# PowerSupply.net
KiCad netlist of a schematic drawn in Altium Designer
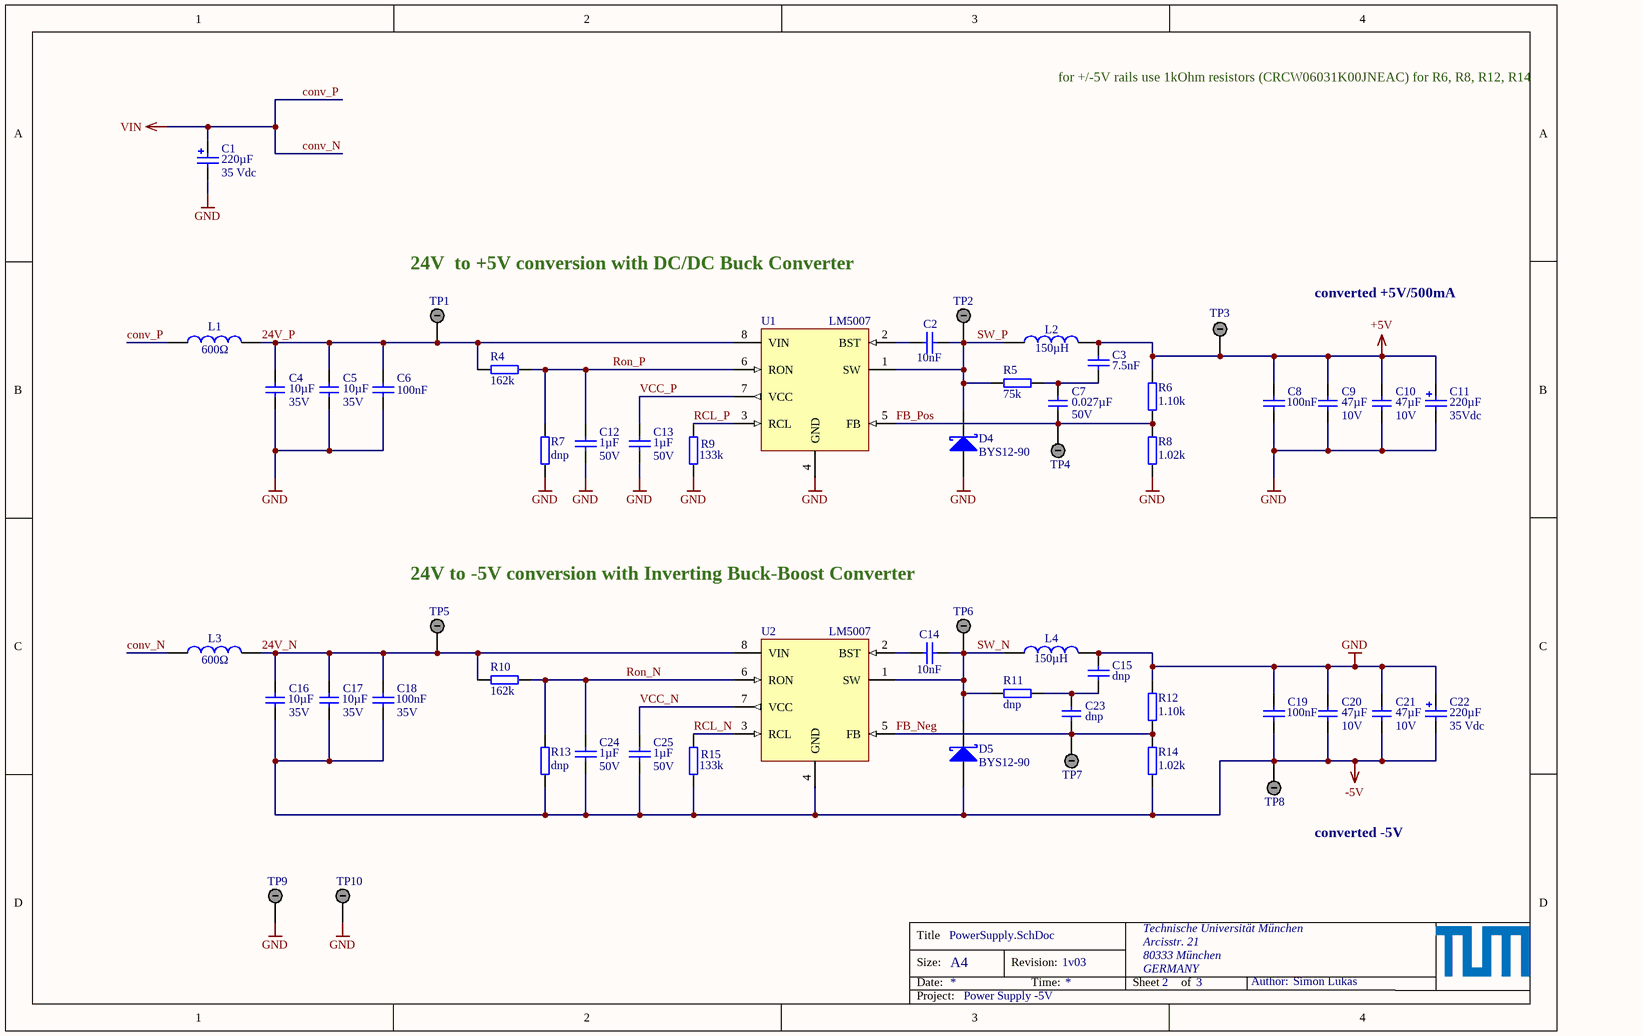
[diagram p0: PowerSupply.SchDoc]

(export (version "E")
  (design (tool "Eeschema 10.0.6"))
  (components
    (comp (ref "C1")
      (value "220µF")
      (footprint "WCAP-ATG5_8x11.5x3.5")
      (description "WCAP-ATG5 Aluminum Electrolytic Capacitors, 8x11.5mm, 35 Vdc, 220 uF")
      (fields
        (field (name "PART NUMBER") "860020574012")
        (field (name "MF") "Würth Elektronik")
        (field (name "VOLTAGE") "35 Vdc")
      )
      (libsource (lib "neg5V") (part "860020574012"))
    )
    (comp (ref "C2")
      (value "10nF")
      (footprint "CAPC1608X07N")
      (fields
        (field (name "MF") "Würth Elektronik")
        (field (name "MPN") "885012206065")
        (field (name "VOLTAGE") "25V")
      )
      (libsource (lib "neg5V") (part "Cap_0603"))
    )
    (comp (ref "C3")
      (value "7.5nF")
      (footprint "CAPC1608X07N")
      (fields
        (field (name "MF") "KEMET")
        (field (name "MPN") "C0603C752J3GACTU")
        (field (name "VOLTAGE") "25V")
      )
      (libsource (lib "neg5V") (part "Cap_0603"))
    )
    (comp (ref "C4")
      (value "10µF")
      (footprint "C_1206")
      (description "Capacitor 1206")
      (fields
        (field (name "TOLERANCE") "10%")
        (field (name "MF") "Murata Electronics")
        (field (name "VOLTAGE") "35V")
      )
      (libsource (lib "neg5V") (part "C_1206"))
    )
    (comp (ref "C5")
      (value "10µF")
      (footprint "C_1206")
      (description "Capacitor 1206")
      (fields
        (field (name "TOLERANCE") "10%")
        (field (name "MF") "Murata Electronics")
        (field (name "VOLTAGE") "35V")
      )
      (libsource (lib "neg5V") (part "C_1206"))
    )
    (comp (ref "C6")
      (value "100nF")
      (footprint "CAPC1608X07N")
      (fields
        (field (name "MF") "Würth Elektronik")
        (field (name "MPN") "885012206071")
        (field (name "VOLTAGE") "25V")
      )
      (libsource (lib "neg5V") (part "Cap_0603"))
    )
    (comp (ref "C7")
      (value "0.027µF")
      (footprint "C_1206")
      (description "Capacitor 1206")
      (fields
        (field (name "TOLERANCE") "5%")
        (field (name "MF") "Murata Electronics")
        (field (name "VOLTAGE") "50V")
      )
      (libsource (lib "neg5V") (part "C_1206"))
    )
    (comp (ref "C8")
      (value "100nF")
      (footprint "CAPC1608X07N")
      (fields
        (field (name "MF") "Würth Elektronik")
        (field (name "MPN") "885012206071")
        (field (name "VOLTAGE") "25V")
      )
      (libsource (lib "neg5V") (part "Cap_0603"))
    )
    (comp (ref "C9")
      (value "47µF")
      (footprint "C_1206")
      (description "Capacitor 1206")
      (fields
        (field (name "TOLERANCE") "20%")
        (field (name "MF") "Murata Electronics")
        (field (name "VOLTAGE") "10V")
      )
      (libsource (lib "neg5V") (part "C_1206"))
    )
    (comp (ref "C10")
      (value "47µF")
      (footprint "C_1206")
      (description "Capacitor 1206")
      (fields
        (field (name "TOLERANCE") "20%")
        (field (name "MF") "Murata Electronics")
        (field (name "VOLTAGE") "10V")
      )
      (libsource (lib "neg5V") (part "C_1206"))
    )
    (comp (ref "C11")
      (value "220µF")
      (footprint "WCAP-ATG5_8x11.5x3.5")
      (description "WCAP-ATG5 Aluminum Electrolytic Capacitors, 8x11.5mm, 35 Vdc, 220 uF")
      (fields
        (field (name "PART NUMBER") "860020574012")
        (field (name "MF") "Würth Elektronik")
        (field (name "VOLTAGE") "35Vdc")
      )
      (libsource (lib "neg5V") (part "860020574012"))
    )
    (comp (ref "C12")
      (value "1µF")
      (footprint "CAPC1608X07N")
      (fields
        (field (name "MF") "Murata Electronics")
        (field (name "MPN") "GRT188R61H105KE13D")
        (field (name "VOLTAGE") "50V")
      )
      (libsource (lib "neg5V") (part "Cap_0603"))
    )
    (comp (ref "C13")
      (value "1µF")
      (footprint "CAPC1608X07N")
      (fields
        (field (name "MF") "Murata Electronics")
        (field (name "MPN") "GRT188R61H105KE13D")
        (field (name "VOLTAGE") "50V")
      )
      (libsource (lib "neg5V") (part "Cap_0603"))
    )
    (comp (ref "C14")
      (value "10nF")
      (footprint "CAPC1608X07N")
      (fields
        (field (name "MF") "Würth Elektronik")
        (field (name "MPN") "885012206065")
        (field (name "VOLTAGE") "25V")
      )
      (libsource (lib "neg5V") (part "Cap_0603"))
    )
    (comp (ref "C15")
      (value "dnp")
      (footprint "CAPC1608X07N")
      (fields
        (field (name "MF") "KEMET")
        (field (name "MPN") "C0603C752J3GACTU")
        (field (name "VOLTAGE") "25V")
      )
      (libsource (lib "neg5V") (part "Cap_0603"))
    )
    (comp (ref "C16")
      (value "10µF")
      (footprint "C_1206")
      (description "Capacitor 1206")
      (fields
        (field (name "TOLERANCE") "10%")
        (field (name "MF") "Murata Electronics")
        (field (name "VOLTAGE") "35V")
      )
      (libsource (lib "neg5V") (part "C_1206"))
    )
    (comp (ref "C17")
      (value "10µF")
      (footprint "C_1206")
      (description "Capacitor 1206")
      (fields
        (field (name "TOLERANCE") "10%")
        (field (name "MF") "Murata Electronics")
        (field (name "VOLTAGE") "35V")
      )
      (libsource (lib "neg5V") (part "C_1206"))
    )
    (comp (ref "C18")
      (value "100nF")
      (footprint "CAPC1608X07N")
      (fields
        (field (name "MF") "Taiyo Yuden")
        (field (name "MPN") "GMK107B7104KAHT")
        (field (name "VOLTAGE") "35V")
        (field (name "TOLERANCE") "10%")
      )
      (libsource (lib "neg5V") (part "Cap_0603"))
    )
    (comp (ref "C19")
      (value "100nF")
      (footprint "CAPC1608X07N")
      (fields
        (field (name "MF") "Würth Elektronik")
        (field (name "MPN") "885012206071")
        (field (name "VOLTAGE") "25V")
      )
      (libsource (lib "neg5V") (part "Cap_0603"))
    )
    (comp (ref "C20")
      (value "47µF")
      (footprint "C_1206")
      (description "Capacitor 1206")
      (fields
        (field (name "TOLERANCE") "20%")
        (field (name "MF") "Murata Electronics")
        (field (name "VOLTAGE") "10V")
      )
      (libsource (lib "neg5V") (part "C_1206"))
    )
    (comp (ref "C21")
      (value "47µF")
      (footprint "C_1206")
      (description "Capacitor 1206")
      (fields
        (field (name "TOLERANCE") "20%")
        (field (name "MF") "Murata Electronics")
        (field (name "VOLTAGE") "10V")
      )
      (libsource (lib "neg5V") (part "C_1206"))
    )
    (comp (ref "C22")
      (value "220µF")
      (footprint "WCAP-ATG5_8x11.5x3.5")
      (description "WCAP-ATG5 Aluminum Electrolytic Capacitors, 8x11.5mm, 35 Vdc, 220 uF")
      (fields
        (field (name "PART NUMBER") "860020574012")
        (field (name "MF") "Würth Elektronik")
        (field (name "VOLTAGE") "35 Vdc")
      )
      (libsource (lib "neg5V") (part "860020574012"))
    )
    (comp (ref "C23")
      (value "dnp")
      (footprint "C_1206")
      (description "Capacitor 1206")
      (fields (field (name "TOLERANCE") "5%") (field (name "MF") "Murata Electronics"))
      (libsource (lib "neg5V") (part "C_1206"))
    )
    (comp (ref "C24")
      (value "1µF")
      (footprint "CAPC1608X07N")
      (fields
        (field (name "MF") "Murata Electronics")
        (field (name "MPN") "GRT188R61H105KE13D")
        (field (name "VOLTAGE") "50V")
      )
      (libsource (lib "neg5V") (part "Cap_0603"))
    )
    (comp (ref "C25")
      (value "1µF")
      (footprint "CAPC1608X07N")
      (fields
        (field (name "MF") "Murata Electronics")
        (field (name "MPN") "GRT188R61H105KE13D")
        (field (name "VOLTAGE") "50V")
      )
      (libsource (lib "neg5V") (part "Cap_0603"))
    )
    (comp (ref "D4")
      (value "BYS12-90")
      (footprint "DIOM4227X23N")
      (description "Schottky Diode")
      (fields (field (name "MF") "Vishay") (field (name "MPN") "BYS12-90-E3/TR3"))
      (libsource (lib "neg5V") (part "BYS12-90"))
    )
    (comp (ref "D5")
      (value "BYS12-90")
      (footprint "DIOM4227X23N")
      (description "Schottky Diode")
      (fields (field (name "MF") "Vishay") (field (name "MPN") "BYS12-90-E3/TR3"))
      (libsource (lib "neg5V") (part "BYS12-90"))
    )
    (comp (ref "L1")
      (value "600Ω")
      (footprint "WE-CBF_0805_High Current")
      (description "WE-CBF SMD EMI Suppression Ferrite Bead, 0805, 600Ω")
      (fields (field (name "MF") "Würth Elektronik") (field (name "MPN") "742792040"))
      (libsource (lib "neg5V") (part "WE-CBF, 742792040"))
    )
    (comp (ref "L2")
      (value "150µH")
      (footprint "SMT_inductor_1050_Performance")
      (description "SMT power Inductor, 150uH, 320m DRC")
      (fields (field (name "MF") "EPCOS / TDK") (field (name "MPN") "B82464G4154M"))
      (libsource (lib "neg5V") (part "B82464G4154M"))
    )
    (comp (ref "L3")
      (value "600Ω")
      (footprint "WE-CBF_0805_High Current")
      (description "WE-CBF SMD EMI Suppression Ferrite Bead, 0805, 600Ω")
      (fields (field (name "MF") "Würth Elektronik") (field (name "MPN") "742792040"))
      (libsource (lib "neg5V") (part "WE-CBF, 742792040"))
    )
    (comp (ref "L4")
      (value "150µH")
      (footprint "SMT_inductor_1050_Performance")
      (description "SMT power Inductor, 150uH, 320m DRC")
      (fields (field (name "MF") "EPCOS / TDK") (field (name "MPN") "B82464G4154M"))
      (libsource (lib "neg5V") (part "B82464G4154M"))
    )
    (comp (ref "R4")
      (value "162k")
      (footprint "RESC1608X06N")
      (fields (field (name "MF") "Bourns") (field (name "MPN") "CR0603-FX-1623ELF"))
      (libsource (lib "neg5V") (part "R_0603"))
    )
    (comp (ref "R5")
      (value "75k")
      (footprint "RESC1608X06N")
      (fields (field (name "MF") "Yageo") (field (name "MPN") "AC0603FR-1375KL"))
      (libsource (lib "neg5V") (part "R_0603"))
    )
    (comp (ref "R6")
      (value "1.10k")
      (footprint "RESC1608X06N")
      (fields
        (field (name "MF") "Vishay / Dale")
        (field (name "MPN") "CRCW06031K10JNEAC")
        (field (name "TOLERANCE") "5%")
      )
      (libsource (lib "neg5V") (part "R_0603"))
    )
    (comp (ref "R7") (value "dnp") (footprint "RESC1608X06N") (libsource (lib "neg5V") (part "R_0603")))
    (comp (ref "R8")
      (value "1.02k")
      (footprint "RESC1608X06N")
      (fields
        (field (name "MF") "Bourns")
        (field (name "MPN") "CR0603-FX-1021ELF")
        (field (name "TOLERANCE") "1%")
      )
      (libsource (lib "neg5V") (part "R_0603"))
    )
    (comp (ref "R9")
      (value "133k")
      (footprint "RESC1608X06N")
      (fields (field (name "MF") "Bourns") (field (name "MPN") "CR0603-FX-1333ELF"))
      (libsource (lib "neg5V") (part "R_0603"))
    )
    (comp (ref "R10")
      (value "162k")
      (footprint "RESC1608X06N")
      (fields (field (name "MF") "Bourns") (field (name "MPN") "CR0603-FX-1623ELF"))
      (libsource (lib "neg5V") (part "R_0603"))
    )
    (comp (ref "R11")
      (value "dnp")
      (footprint "RESC1608X06N")
      (fields (field (name "MF") "Yageo") (field (name "MPN") "AC0603FR-1375KL"))
      (libsource (lib "neg5V") (part "R_0603"))
    )
    (comp (ref "R12")
      (value "1.10k")
      (footprint "RESC1608X06N")
      (fields
        (field (name "MF") "Vishay / Dale")
        (field (name "MPN") "CRCW06031K10JNEAC")
        (field (name "TOLERANCE") "5%")
      )
      (libsource (lib "neg5V") (part "R_0603"))
    )
    (comp (ref "R13") (value "dnp") (footprint "RESC1608X06N") (libsource (lib "neg5V") (part "R_0603")))
    (comp (ref "R14")
      (value "1.02k")
      (footprint "RESC1608X06N")
      (fields
        (field (name "MF") "Bourns")
        (field (name "MPN") "CR0603-FX-1021ELF")
        (field (name "TOLERANCE") "1%")
      )
      (libsource (lib "neg5V") (part "R_0603"))
    )
    (comp (ref "R15")
      (value "133k")
      (footprint "RESC1608X06N")
      (fields (field (name "MF") "Bourns") (field (name "MPN") "CR0603-FX-1333ELF"))
      (libsource (lib "neg5V") (part "R_0603"))
    )
    (comp (ref "TP1")
      (value "24V_P")
      (footprint "TP_5006")
      (description "Test Point;  Compact;  THM;  PC;  .350 L;  .125 OD;  Heat Resistant Nylon 46;  Black")
      (fields
        (field (name "MANUFACTURER") "Keystone Electronics")
        (field (name "MANUFACTURER PART NUMBER") "5006")
      )
      (libsource (lib "neg5V") (part "5006"))
    )
    (comp (ref "TP2")
      (value "SW_P")
      (footprint "TP_5006")
      (description "Test Point;  Compact;  THM;  PC;  .350 L;  .125 OD;  Heat Resistant Nylon 46;  Black")
      (fields
        (field (name "MANUFACTURER") "Keystone Electronics")
        (field (name "MANUFACTURER PART NUMBER") "5006")
      )
      (libsource (lib "neg5V") (part "5006"))
    )
    (comp (ref "TP3")
      (value "+5V")
      (footprint "TP_5006")
      (description "Test Point;  Compact;  THM;  PC;  .350 L;  .125 OD;  Heat Resistant Nylon 46;  Black")
      (fields
        (field (name "MANUFACTURER") "Keystone Electronics")
        (field (name "MANUFACTURER PART NUMBER") "5006")
      )
      (libsource (lib "neg5V") (part "5006"))
    )
    (comp (ref "TP4")
      (value "FB_P")
      (footprint "TP_5006")
      (description "Test Point;  Compact;  THM;  PC;  .350 L;  .125 OD;  Heat Resistant Nylon 46;  Black")
      (fields
        (field (name "MANUFACTURER") "Keystone Electronics")
        (field (name "MANUFACTURER PART NUMBER") "5006")
      )
      (libsource (lib "neg5V") (part "5006"))
    )
    (comp (ref "TP5")
      (value "24V_N")
      (footprint "TP_5006")
      (description "Test Point;  Compact;  THM;  PC;  .350 L;  .125 OD;  Heat Resistant Nylon 46;  Black")
      (fields
        (field (name "MANUFACTURER") "Keystone Electronics")
        (field (name "MANUFACTURER PART NUMBER") "5006")
      )
      (libsource (lib "neg5V") (part "5006"))
    )
    (comp (ref "TP6")
      (value "SW_N")
      (footprint "TP_5006")
      (description "Test Point;  Compact;  THM;  PC;  .350 L;  .125 OD;  Heat Resistant Nylon 46;  Black")
      (fields
        (field (name "MANUFACTURER") "Keystone Electronics")
        (field (name "MANUFACTURER PART NUMBER") "5006")
      )
      (libsource (lib "neg5V") (part "5006"))
    )
    (comp (ref "TP7")
      (value "FB_N")
      (footprint "TP_5006")
      (description "Test Point;  Compact;  THM;  PC;  .350 L;  .125 OD;  Heat Resistant Nylon 46;  Black")
      (fields
        (field (name "MANUFACTURER") "Keystone Electronics")
        (field (name "MANUFACTURER PART NUMBER") "5006")
      )
      (libsource (lib "neg5V") (part "5006"))
    )
    (comp (ref "TP8")
      (value "-5V")
      (footprint "TP_5006")
      (description "Test Point;  Compact;  THM;  PC;  .350 L;  .125 OD;  Heat Resistant Nylon 46;  Black")
      (fields
        (field (name "MANUFACTURER") "Keystone Electronics")
        (field (name "MANUFACTURER PART NUMBER") "5006")
      )
      (libsource (lib "neg5V") (part "5006"))
    )
    (comp (ref "TP9")
      (value "GND")
      (footprint "TP_5006")
      (description "Test Point;  Compact;  THM;  PC;  .350 L;  .125 OD;  Heat Resistant Nylon 46;  Black")
      (fields
        (field (name "MANUFACTURER") "Keystone Electronics")
        (field (name "MANUFACTURER PART NUMBER") "5006")
      )
      (libsource (lib "neg5V") (part "5006"))
    )
    (comp (ref "TP10")
      (value "GND")
      (footprint "TP_5006")
      (description "Test Point;  Compact;  THM;  PC;  .350 L;  .125 OD;  Heat Resistant Nylon 46;  Black")
      (fields
        (field (name "MANUFACTURER") "Keystone Electronics")
        (field (name "MANUFACTURER PART NUMBER") "5006")
      )
      (libsource (lib "neg5V") (part "5006"))
    )
    (comp (ref "U1")
      (value "LM5007")
      (footprint "TSOP65P490X110-8N")
      (description "Buck Converter, 9-75Vin, 2.5-73Vout")
      (fields (field (name "MF") "Texas Instruments") (field (name "MPN") "LM5007MM/NOPB"))
      (libsource (lib "neg5V") (part "LM5007"))
    )
    (comp (ref "U2")
      (value "LM5007")
      (footprint "TSOP65P490X110-8N")
      (description "Buck Converter, 9-75Vin, 2.5-73Vout")
      (fields (field (name "MF") "Texas Instruments") (field (name "MPN") "LM5007MM/NOPB"))
      (libsource (lib "neg5V") (part "LM5007"))
    )
  )
  (nets
    (net (code "1") (name "+5V") (class "Default")
      (node (ref "C10") (pin "2") (pinfunction "2_2") (pintype "passive"))
      (node (ref "C11") (pin "1") (pinfunction "P_1") (pintype "passive"))
      (node (ref "C3") (pin "1") (pinfunction "1_1") (pintype "passive"))
      (node (ref "C8") (pin "2") (pinfunction "2_2") (pintype "passive"))
      (node (ref "C9") (pin "2") (pinfunction "2_2") (pintype "passive"))
      (node (ref "L2") (pin "2") (pinfunction "2_2") (pintype "passive"))
      (node (ref "R6") (pin "2") (pintype "passive"))
      (node (ref "TP3") (pin "1") (pintype "passive"))
    )
    (net (code "2") (name "-5V") (class "Default")
      (node (ref "C16") (pin "1") (pinfunction "1_1") (pintype "passive"))
      (node (ref "C17") (pin "1") (pinfunction "1_1") (pintype "passive"))
      (node (ref "C18") (pin "2") (pinfunction "2_2") (pintype "passive"))
      (node (ref "C19") (pin "1") (pinfunction "1_1") (pintype "passive"))
      (node (ref "C20") (pin "1") (pinfunction "1_1") (pintype "passive"))
      (node (ref "C21") (pin "1") (pinfunction "1_1") (pintype "passive"))
      (node (ref "C22") (pin "2") (pinfunction "N_2") (pintype "passive"))
      (node (ref "C24") (pin "2") (pinfunction "2_2") (pintype "passive"))
      (node (ref "C25") (pin "2") (pinfunction "2_2") (pintype "passive"))
      (node (ref "D5") (pin "2") (pinfunction "A_2") (pintype "passive"))
      (node (ref "R13") (pin "1") (pintype "passive"))
      (node (ref "R14") (pin "2") (pintype "passive"))
      (node (ref "R15") (pin "1") (pintype "passive"))
      (node (ref "TP8") (pin "1") (pintype "passive"))
      (node (ref "U2") (pin "4") (pinfunction "GND_4") (pintype "power_in"))
    )
    (net (code "3") (name "/24V_N") (class "Default")
      (node (ref "C16") (pin "2") (pinfunction "2_2") (pintype "passive"))
      (node (ref "C17") (pin "2") (pinfunction "2_2") (pintype "passive"))
      (node (ref "C18") (pin "1") (pinfunction "1_1") (pintype "passive"))
      (node (ref "L3") (pin "2") (pinfunction "2_2") (pintype "passive"))
      (node (ref "R10") (pin "2") (pintype "passive"))
      (node (ref "TP5") (pin "1") (pintype "passive"))
      (node (ref "U2") (pin "8") (pinfunction "VIN_8") (pintype "power_in"))
    )
    (net (code "4") (name "/24V_P") (class "Default")
      (node (ref "C4") (pin "2") (pinfunction "2_2") (pintype "passive"))
      (node (ref "C5") (pin "2") (pinfunction "2_2") (pintype "passive"))
      (node (ref "C6") (pin "1") (pinfunction "1_1") (pintype "passive"))
      (node (ref "L1") (pin "2") (pinfunction "2_2") (pintype "passive"))
      (node (ref "R4") (pin "1") (pintype "passive"))
      (node (ref "TP1") (pin "1") (pintype "passive"))
      (node (ref "U1") (pin "8") (pinfunction "VIN_8") (pintype "power_in"))
    )
    (net (code "5") (name "/FB_Neg") (class "Default")
      (node (ref "C23") (pin "2") (pinfunction "2_2") (pintype "passive"))
      (node (ref "R12") (pin "2") (pintype "passive"))
      (node (ref "R14") (pin "1") (pintype "passive"))
      (node (ref "TP7") (pin "1") (pintype "passive"))
      (node (ref "U2") (pin "5") (pinfunction "FB_5") (pintype "input"))
    )
    (net (code "6") (name "/FB_Pos") (class "Default")
      (node (ref "C7") (pin "1") (pinfunction "1_1") (pintype "passive"))
      (node (ref "R6") (pin "1") (pintype "passive"))
      (node (ref "R8") (pin "2") (pintype "passive"))
      (node (ref "TP4") (pin "1") (pintype "passive"))
      (node (ref "U1") (pin "5") (pinfunction "FB_5") (pintype "input"))
    )
    (net (code "7") (name "/RCL_N") (class "Default")
      (node (ref "R15") (pin "2") (pintype "passive"))
      (node (ref "U2") (pin "3") (pinfunction "RCL_3") (pintype "input"))
    )
    (net (code "8") (name "/RCL_P") (class "Default")
      (node (ref "R9") (pin "2") (pintype "passive"))
      (node (ref "U1") (pin "3") (pinfunction "RCL_3") (pintype "input"))
    )
    (net (code "9") (name "/Ron_N") (class "Default")
      (node (ref "C24") (pin "1") (pinfunction "1_1") (pintype "passive"))
      (node (ref "R10") (pin "1") (pintype "passive"))
      (node (ref "R13") (pin "2") (pintype "passive"))
      (node (ref "U2") (pin "6") (pinfunction "RON_6") (pintype "input"))
    )
    (net (code "10") (name "/Ron_P") (class "Default")
      (node (ref "C12") (pin "1") (pinfunction "1_1") (pintype "passive"))
      (node (ref "R4") (pin "2") (pintype "passive"))
      (node (ref "R7") (pin "2") (pintype "passive"))
      (node (ref "U1") (pin "6") (pinfunction "RON_6") (pintype "input"))
    )
    (net (code "11") (name "/SW_N") (class "Default")
      (node (ref "C14") (pin "1") (pinfunction "1_1") (pintype "passive"))
      (node (ref "D5") (pin "1") (pinfunction "K_1") (pintype "passive"))
      (node (ref "L4") (pin "1") (pinfunction "1_1") (pintype "passive"))
      (node (ref "R11") (pin "2") (pintype "passive"))
      (node (ref "TP6") (pin "1") (pintype "passive"))
      (node (ref "U2") (pin "1") (pinfunction "SW_1") (pintype "power_in"))
    )
    (net (code "12") (name "/SW_P") (class "Default")
      (node (ref "C2") (pin "2") (pinfunction "2_2") (pintype "passive"))
      (node (ref "D4") (pin "1") (pinfunction "K_1") (pintype "passive"))
      (node (ref "L2") (pin "1") (pinfunction "1_1") (pintype "passive"))
      (node (ref "R5") (pin "1") (pintype "passive"))
      (node (ref "TP2") (pin "1") (pintype "passive"))
      (node (ref "U1") (pin "1") (pinfunction "SW_1") (pintype "power_in"))
    )
    (net (code "13") (name "/VCC_N") (class "Default")
      (node (ref "C25") (pin "1") (pinfunction "1_1") (pintype "passive"))
      (node (ref "U2") (pin "7") (pinfunction "VCC_7") (pintype "output"))
    )
    (net (code "14") (name "/VCC_P") (class "Default")
      (node (ref "C13") (pin "1") (pinfunction "1_1") (pintype "passive"))
      (node (ref "U1") (pin "7") (pinfunction "VCC_7") (pintype "output"))
    )
    (net (code "15") (name "GND") (class "Default")
      (node (ref "C1") (pin "2") (pinfunction "N_2") (pintype "passive"))
      (node (ref "C10") (pin "1") (pinfunction "1_1") (pintype "passive"))
      (node (ref "C11") (pin "2") (pinfunction "N_2") (pintype "passive"))
      (node (ref "C12") (pin "2") (pinfunction "2_2") (pintype "passive"))
      (node (ref "C13") (pin "2") (pinfunction "2_2") (pintype "passive"))
      (node (ref "C15") (pin "1") (pinfunction "1_1") (pintype "passive"))
      (node (ref "C19") (pin "2") (pinfunction "2_2") (pintype "passive"))
      (node (ref "C20") (pin "2") (pinfunction "2_2") (pintype "passive"))
      (node (ref "C21") (pin "2") (pinfunction "2_2") (pintype "passive"))
      (node (ref "C22") (pin "1") (pinfunction "P_1") (pintype "passive"))
      (node (ref "C4") (pin "1") (pinfunction "1_1") (pintype "passive"))
      (node (ref "C5") (pin "1") (pinfunction "1_1") (pintype "passive"))
      (node (ref "C6") (pin "2") (pinfunction "2_2") (pintype "passive"))
      (node (ref "C8") (pin "1") (pinfunction "1_1") (pintype "passive"))
      (node (ref "C9") (pin "1") (pinfunction "1_1") (pintype "passive"))
      (node (ref "D4") (pin "2") (pinfunction "A_2") (pintype "passive"))
      (node (ref "L4") (pin "2") (pinfunction "2_2") (pintype "passive"))
      (node (ref "R12") (pin "1") (pintype "passive"))
      (node (ref "R7") (pin "1") (pintype "passive"))
      (node (ref "R8") (pin "1") (pintype "passive"))
      (node (ref "R9") (pin "1") (pintype "passive"))
      (node (ref "TP10") (pin "1") (pintype "passive"))
      (node (ref "TP9") (pin "1") (pintype "passive"))
      (node (ref "U1") (pin "4") (pinfunction "GND_4") (pintype "power_in"))
    )
    (net (code "16") (name "Net-(C3-Pad2)") (class "Default")
      (node (ref "C3") (pin "2") (pinfunction "2_2") (pintype "passive"))
      (node (ref "C7") (pin "2") (pinfunction "2_2") (pintype "passive"))
      (node (ref "R5") (pin "2") (pintype "passive"))
    )
    (net (code "17") (name "Net-(C15-Pad2)") (class "Default")
      (node (ref "C15") (pin "2") (pinfunction "2_2") (pintype "passive"))
      (node (ref "C23") (pin "1") (pinfunction "1_1") (pintype "passive"))
      (node (ref "R11") (pin "1") (pintype "passive"))
    )
    (net (code "18") (name "Net-(U1-BST)") (class "Default")
      (node (ref "C2") (pin "1") (pinfunction "1_1") (pintype "passive"))
      (node (ref "U1") (pin "2") (pinfunction "BST_2") (pintype "input"))
    )
    (net (code "19") (name "Net-(U2-BST)") (class "Default")
      (node (ref "C14") (pin "2") (pinfunction "2_2") (pintype "passive"))
      (node (ref "U2") (pin "2") (pinfunction "BST_2") (pintype "input"))
    )
    (net (code "20") (name "VIN") (class "Default")
      (node (ref "C1") (pin "1") (pinfunction "P_1") (pintype "passive"))
      (node (ref "L1") (pin "1") (pinfunction "1_1") (pintype "passive"))
      (node (ref "L3") (pin "1") (pinfunction "1_1") (pintype "passive"))
    )
  )
)
